# rev1.net
KiCad netlist of a schematic drawn in EAGLE
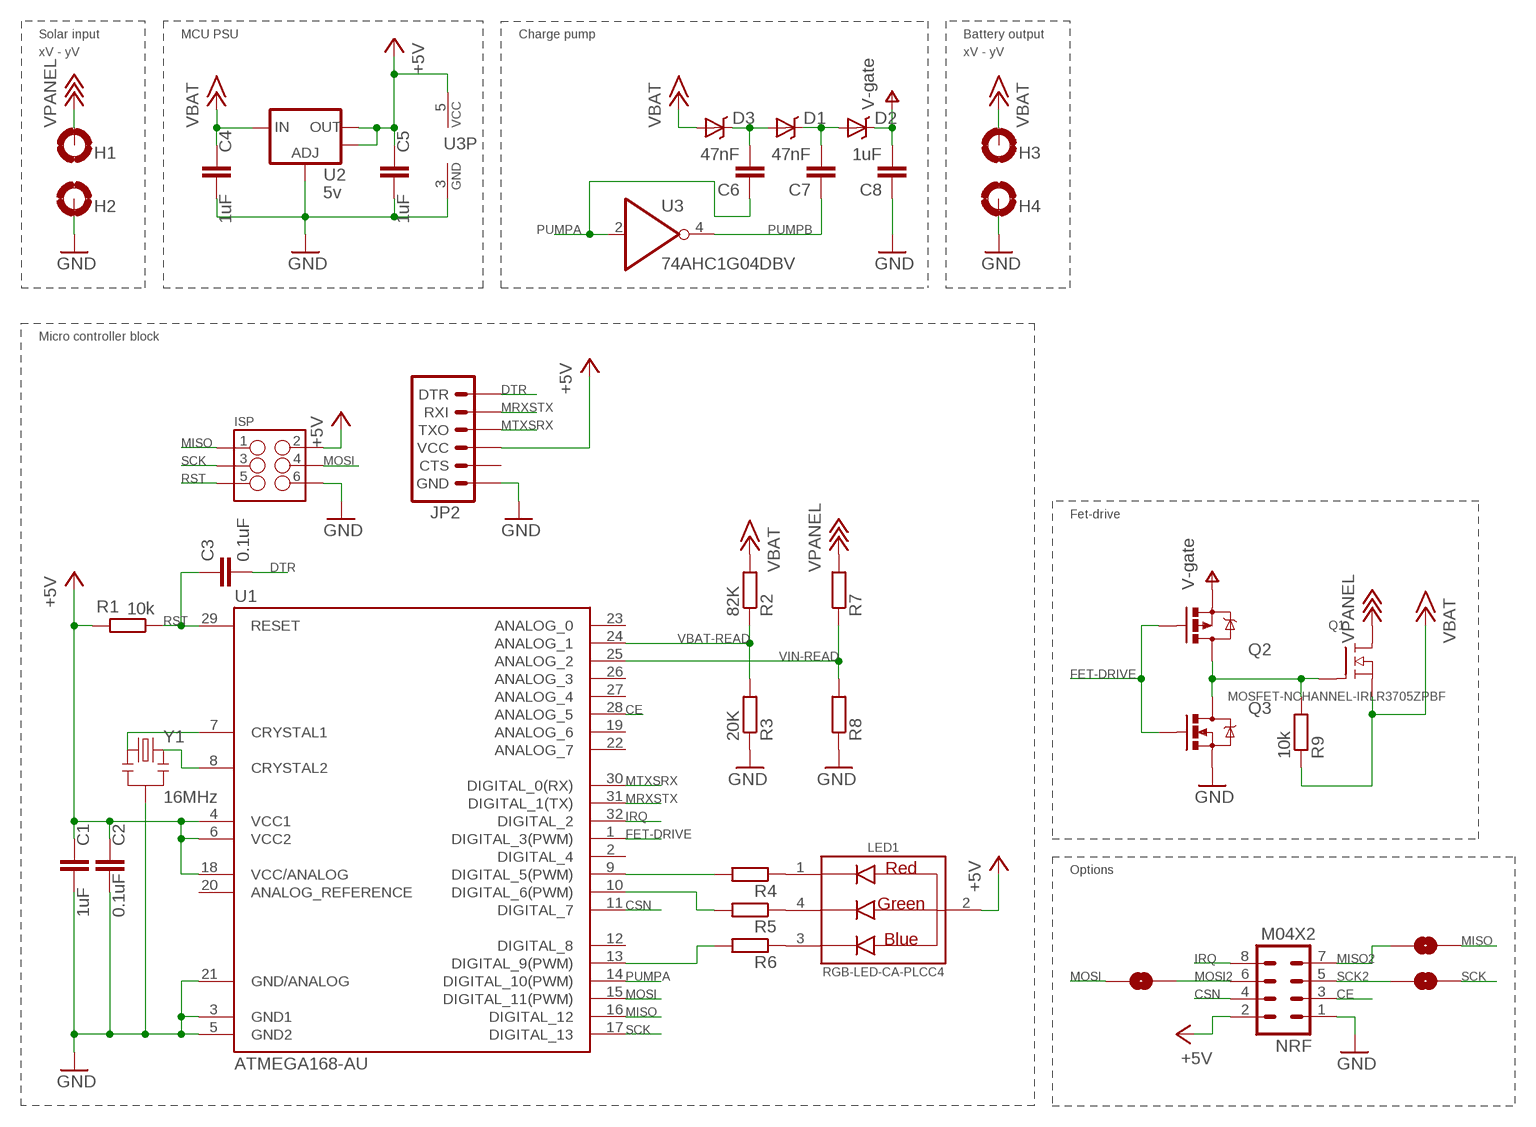
[diagram p0: schematic, sheet 1]

(export (version "E")
  (design (tool "Eeschema 10.0.6"))
  (components
    (comp (ref "C1")
      (value "1uF")
      (footprint "eagle-import:C0603K")
      (libsource (lib "eagle-import") (part "C-EUC0603K"))
    )
    (comp (ref "C2")
      (value "0.1uF")
      (footprint "eagle-import:C0603K")
      (libsource (lib "eagle-import") (part "C-EUC0603K"))
    )
    (comp (ref "C3")
      (value "0.1uF")
      (footprint "eagle-import:C0603K")
      (libsource (lib "eagle-import") (part "C-EUC0603K"))
    )
    (comp (ref "C4")
      (value "1uF")
      (footprint "eagle-import:C0603K")
      (libsource (lib "eagle-import") (part "C-EUC0603K"))
    )
    (comp (ref "C5")
      (value "1uF")
      (footprint "eagle-import:C0603K")
      (libsource (lib "eagle-import") (part "C-EUC0603K"))
    )
    (comp (ref "C6")
      (value "47nF")
      (footprint "eagle-import:C0603K")
      (libsource (lib "eagle-import") (part "C-EUC0603K"))
    )
    (comp (ref "C7")
      (value "47nF")
      (footprint "eagle-import:C0603K")
      (libsource (lib "eagle-import") (part "C-EUC0603K"))
    )
    (comp (ref "C8")
      (value "1uF")
      (footprint "eagle-import:C0603K")
      (libsource (lib "eagle-import") (part "C-EUC0603K"))
    )
    (comp (ref "D1")
      (value "DIODE-SCHOTTKY")
      (footprint "eagle-import:SOD-523")
      (libsource (lib "eagle-import") (part "DIODE-SCHOTTKY"))
    )
    (comp (ref "D2")
      (value "DIODE-SCHOTTKY")
      (footprint "eagle-import:SOD-523")
      (libsource (lib "eagle-import") (part "DIODE-SCHOTTKY"))
    )
    (comp (ref "D3")
      (value "DIODE-SCHOTTKY")
      (footprint "eagle-import:SOD-523")
      (libsource (lib "eagle-import") (part "DIODE-SCHOTTKY"))
    )
    (comp (ref "H1")
      (value "MOUNT-PAD-ROUND3.0")
      (footprint "eagle-import:3,0-PAD")
      (libsource (lib "eagle-import") (part "MOUNT-PAD-ROUND3.0"))
    )
    (comp (ref "H2")
      (value "MOUNT-PAD-ROUND3.0")
      (footprint "eagle-import:3,0-PAD")
      (libsource (lib "eagle-import") (part "MOUNT-PAD-ROUND3.0"))
    )
    (comp (ref "H3")
      (value "MOUNT-PAD-ROUND3.0")
      (footprint "eagle-import:3,0-PAD")
      (libsource (lib "eagle-import") (part "MOUNT-PAD-ROUND3.0"))
    )
    (comp (ref "H4")
      (value "MOUNT-PAD-ROUND3.0")
      (footprint "eagle-import:3,0-PAD")
      (libsource (lib "eagle-import") (part "MOUNT-PAD-ROUND3.0"))
    )
    (comp (ref "ISP")
      (value "M03X22X3_SILK_SM")
      (footprint "eagle-import:2X3")
      (libsource (lib "eagle-import") (part "M03X22X3_SILK_SM"))
    )
    (comp (ref "JP2")
      (value "ARDUINO_SERIAL_PROGRAMLOCK")
      (footprint "eagle-import:1X06_LOCK")
      (libsource (lib "eagle-import") (part "ARDUINO_SERIAL_PROGRAMLOCK"))
    )
    (comp (ref "LED1")
      (value "RGB-LED-CA-PLCC4")
      (footprint "eagle-import:PLCC4")
      (libsource (lib "eagle-import") (part "RGB-LED-CA-PLCC4"))
    )
    (comp (ref "NRF")
      (value "M04X2")
      (footprint "eagle-import:2X4")
      (libsource (lib "eagle-import") (part "M04X2"))
    )
    (comp (ref "Q1")
      (value "MOSFET-NCHANNEL-IRLR3705ZPBF")
      (footprint "eagle-import:DPAK")
      (libsource (lib "eagle-import") (part "MOSFET-NCHANNEL-IRLR3705ZPBF"))
    )
    (comp (ref "Q2")
      (value "MOSFET-PCHANNEL")
      (footprint "eagle-import:SOT23")
      (libsource (lib "eagle-import") (part "MOSFET-PCHANNEL"))
    )
    (comp (ref "Q3")
      (value "MOSFET-NCHANNELBSS138")
      (footprint "eagle-import:SOT23")
      (libsource (lib "eagle-import") (part "MOSFET-NCHANNELBSS138"))
    )
    (comp (ref "R1")
      (value "10k")
      (footprint "eagle-import:R0603")
      (libsource (lib "eagle-import") (part "R-EU_R0603"))
    )
    (comp (ref "R2")
      (value "82K")
      (footprint "eagle-import:R0603")
      (libsource (lib "eagle-import") (part "R-EU_R0603"))
    )
    (comp (ref "R3")
      (value "20K")
      (footprint "eagle-import:R0603")
      (libsource (lib "eagle-import") (part "R-EU_R0603"))
    )
    (comp (ref "R4")
      (value "R-EU_R0603")
      (footprint "eagle-import:R0603")
      (libsource (lib "eagle-import") (part "R-EU_R0603"))
    )
    (comp (ref "R5")
      (value "R-EU_R0603")
      (footprint "eagle-import:R0603")
      (libsource (lib "eagle-import") (part "R-EU_R0603"))
    )
    (comp (ref "R6")
      (value "R-EU_R0603")
      (footprint "eagle-import:R0603")
      (libsource (lib "eagle-import") (part "R-EU_R0603"))
    )
    (comp (ref "R7")
      (value "R-EU_R0603")
      (footprint "eagle-import:R0603")
      (libsource (lib "eagle-import") (part "R-EU_R0603"))
    )
    (comp (ref "R8")
      (value "R-EU_R0603")
      (footprint "eagle-import:R0603")
      (libsource (lib "eagle-import") (part "R-EU_R0603"))
    )
    (comp (ref "R9")
      (value "10k")
      (footprint "eagle-import:R0603")
      (libsource (lib "eagle-import") (part "R-EU_R0603"))
    )
    (comp (ref "SJ2")
      (value "SOLDERJUMPERNO")
      (footprint "eagle-import:SJ_2S-NO")
      (libsource (lib "eagle-import") (part "SOLDERJUMPERNO"))
    )
    (comp (ref "SJ5")
      (value "SOLDERJUMPERNO")
      (footprint "eagle-import:SJ_2S-NO")
      (libsource (lib "eagle-import") (part "SOLDERJUMPERNO"))
    )
    (comp (ref "SJ6")
      (value "SOLDERJUMPERNO")
      (footprint "eagle-import:SJ_2S-NO")
      (libsource (lib "eagle-import") (part "SOLDERJUMPERNO"))
    )
    (comp (ref "U1")
      (value "ATMEGA168-AU")
      (footprint "eagle-import:TQFP32-08")
      (libsource (lib "eagle-import") (part "ATMEGA168-AU"))
    )
    (comp (ref "U2")
      (value "5v")
      (footprint "eagle-import:SOT223")
      (libsource (lib "eagle-import") (part "V_REG_LM1117SOT223"))
    )
    (comp (ref "U3")
      (value "74AHC1G04DBV")
      (footprint "eagle-import:SOT23-5")
      (libsource (lib "eagle-import") (part "741G04DBVAHC"))
    )
    (comp (ref "Y1")
      (value "16MHz")
      (footprint "eagle-import:RESONATOR-SMD")
      (libsource (lib "eagle-import") (part "RESONATOR16MHZ"))
    )
  )
  (nets
    (net (code "1") (name "+5V") (class "Default")
      (node (ref "C1") (pin "1") (pinfunction "1_1") (pintype "passive"))
      (node (ref "C2") (pin "1") (pinfunction "1_1") (pintype "passive"))
      (node (ref "C5") (pin "1") (pinfunction "1_1") (pintype "passive"))
      (node (ref "ISP") (pin "2") (pinfunction "2_2") (pintype "bidirectional"))
      (node (ref "JP2") (pin "4") (pinfunction "VCC_4") (pintype "passive"))
      (node (ref "LED1") (pin "2") (pinfunction "CA_2") (pintype "bidirectional"))
      (node (ref "NRF") (pin "2") (pinfunction "2_2") (pintype "passive"))
      (node (ref "R1") (pin "2") (pinfunction "2_2") (pintype "passive"))
      (node (ref "U1") (pin "18") (pinfunction "VCC/ANALOG_18") (pintype "passive"))
      (node (ref "U1") (pin "4") (pinfunction "VCC1_4") (pintype "power_in"))
      (node (ref "U1") (pin "6") (pinfunction "VCC2_6") (pintype "power_in"))
      (node (ref "U2") (pin "2") (pinfunction "OUT_2") (pintype "output"))
      (node (ref "U2") (pin "4") (pinfunction "OUT_4") (pintype "output"))
      (node (ref "U3") (pin "5") (pinfunction "VCC_5") (pintype "power_in"))
    )
    (net (code "2") (name "/CE") (class "Default")
      (node (ref "NRF") (pin "3") (pinfunction "3_3") (pintype "passive"))
      (node (ref "U1") (pin "28") (pinfunction "ANALOG_5_28") (pintype "bidirectional"))
    )
    (net (code "3") (name "/CSN") (class "Default")
      (node (ref "NRF") (pin "4") (pinfunction "4_4") (pintype "passive"))
      (node (ref "U1") (pin "11") (pinfunction "DIGITAL_7_11") (pintype "bidirectional"))
    )
    (net (code "4") (name "/DTR") (class "Default")
      (node (ref "C3") (pin "2") (pinfunction "2_2") (pintype "passive"))
      (node (ref "JP2") (pin "1") (pinfunction "DTR_1") (pintype "passive"))
    )
    (net (code "5") (name "/FET-DRIVE") (class "Default")
      (node (ref "Q2") (pin "1") (pinfunction "G_1") (pintype "passive"))
      (node (ref "Q3") (pin "1") (pinfunction "G_1") (pintype "passive"))
      (node (ref "U1") (pin "1") (pinfunction "DIGITAL_3(PWM)_1") (pintype "bidirectional"))
    )
    (net (code "6") (name "/IRQ") (class "Default")
      (node (ref "NRF") (pin "8") (pinfunction "8_8") (pintype "passive"))
      (node (ref "U1") (pin "32") (pinfunction "DIGITAL_2_32") (pintype "bidirectional"))
    )
    (net (code "7") (name "/MISO") (class "Default")
      (node (ref "ISP") (pin "1") (pinfunction "1_1") (pintype "bidirectional"))
      (node (ref "SJ6") (pin "2") (pinfunction "2_2") (pintype "passive"))
      (node (ref "U1") (pin "16") (pinfunction "DIGITAL_12_16") (pintype "bidirectional"))
    )
    (net (code "8") (name "/MISO2") (class "Default")
      (node (ref "NRF") (pin "7") (pinfunction "7_7") (pintype "passive"))
      (node (ref "SJ6") (pin "1") (pinfunction "1_1") (pintype "passive"))
    )
    (net (code "9") (name "/MOSI") (class "Default")
      (node (ref "ISP") (pin "4") (pinfunction "4_4") (pintype "bidirectional"))
      (node (ref "SJ2") (pin "1") (pinfunction "1_1") (pintype "passive"))
      (node (ref "U1") (pin "15") (pinfunction "DIGITAL_11(PWM)_15") (pintype "bidirectional"))
    )
    (net (code "10") (name "/MOSI2") (class "Default")
      (node (ref "NRF") (pin "6") (pinfunction "6_6") (pintype "passive"))
      (node (ref "SJ2") (pin "2") (pinfunction "2_2") (pintype "passive"))
    )
    (net (code "11") (name "/MRXSTX") (class "Default")
      (node (ref "JP2") (pin "2") (pinfunction "RXI_2") (pintype "passive"))
      (node (ref "U1") (pin "31") (pinfunction "DIGITAL_1(TX)_31") (pintype "bidirectional"))
    )
    (net (code "12") (name "/MTXSRX") (class "Default")
      (node (ref "JP2") (pin "3") (pinfunction "TXO_3") (pintype "passive"))
      (node (ref "U1") (pin "30") (pinfunction "DIGITAL_0(RX)_30") (pintype "bidirectional"))
    )
    (net (code "13") (name "/PUMPA") (class "Default")
      (node (ref "C6") (pin "1") (pinfunction "1_1") (pintype "passive"))
      (node (ref "U1") (pin "14") (pinfunction "DIGITAL_10(PWM)_14") (pintype "bidirectional"))
      (node (ref "U3") (pin "2") (pinfunction "I_2") (pintype "input"))
    )
    (net (code "14") (name "/PUMPB") (class "Default")
      (node (ref "C7") (pin "1") (pinfunction "1_1") (pintype "passive"))
      (node (ref "U3") (pin "4") (pinfunction "O_4") (pintype "output"))
    )
    (net (code "15") (name "/RST") (class "Default")
      (node (ref "C3") (pin "1") (pinfunction "1_1") (pintype "passive"))
      (node (ref "ISP") (pin "5") (pinfunction "5_5") (pintype "bidirectional"))
      (node (ref "R1") (pin "1") (pinfunction "1_1") (pintype "passive"))
      (node (ref "U1") (pin "29") (pinfunction "RESET_29") (pintype "bidirectional"))
    )
    (net (code "16") (name "/SCK") (class "Default")
      (node (ref "ISP") (pin "3") (pinfunction "3_3") (pintype "bidirectional"))
      (node (ref "SJ5") (pin "2") (pinfunction "2_2") (pintype "passive"))
      (node (ref "U1") (pin "17") (pinfunction "DIGITAL_13_17") (pintype "bidirectional"))
    )
    (net (code "17") (name "/SCK2") (class "Default")
      (node (ref "NRF") (pin "5") (pinfunction "5_5") (pintype "passive"))
      (node (ref "SJ5") (pin "1") (pinfunction "1_1") (pintype "passive"))
    )
    (net (code "18") (name "/VBAT-READ") (class "Default")
      (node (ref "R2") (pin "1") (pinfunction "1_1") (pintype "passive"))
      (node (ref "R3") (pin "2") (pinfunction "2_2") (pintype "passive"))
      (node (ref "U1") (pin "24") (pinfunction "ANALOG_1_24") (pintype "bidirectional"))
    )
    (net (code "19") (name "/VIN-READ") (class "Default")
      (node (ref "R7") (pin "1") (pinfunction "1_1") (pintype "passive"))
      (node (ref "R8") (pin "2") (pinfunction "2_2") (pintype "passive"))
      (node (ref "U1") (pin "25") (pinfunction "ANALOG_2_25") (pintype "bidirectional"))
    )
    (net (code "20") (name "GND") (class "Default")
      (node (ref "C1") (pin "2") (pinfunction "2_2") (pintype "passive"))
      (node (ref "C2") (pin "2") (pinfunction "2_2") (pintype "passive"))
      (node (ref "C4") (pin "2") (pinfunction "2_2") (pintype "passive"))
      (node (ref "C5") (pin "2") (pinfunction "2_2") (pintype "passive"))
      (node (ref "C8") (pin "1") (pinfunction "1_1") (pintype "passive"))
      (node (ref "H2") (pin "B3,0") (pinfunction "MOUNT_B3,0") (pintype "passive"))
      (node (ref "H4") (pin "B3,0") (pinfunction "MOUNT_B3,0") (pintype "passive"))
      (node (ref "ISP") (pin "6") (pinfunction "6_6") (pintype "bidirectional"))
      (node (ref "JP2") (pin "6") (pinfunction "GND_6") (pintype "passive"))
      (node (ref "NRF") (pin "1") (pinfunction "1_1") (pintype "passive"))
      (node (ref "Q3") (pin "2") (pinfunction "S_2") (pintype "passive"))
      (node (ref "R3") (pin "1") (pinfunction "1_1") (pintype "passive"))
      (node (ref "R8") (pin "1") (pinfunction "1_1") (pintype "passive"))
      (node (ref "U1") (pin "21") (pinfunction "GND/ANALOG_21") (pintype "power_in"))
      (node (ref "U1") (pin "3") (pinfunction "GND1_3") (pintype "power_in"))
      (node (ref "U1") (pin "5") (pinfunction "GND2_5") (pintype "power_in"))
      (node (ref "U2") (pin "1") (pinfunction "ADJ_1") (pintype "input"))
      (node (ref "U3") (pin "3") (pinfunction "GND_3") (pintype "power_in"))
      (node (ref "Y1") (pin "2") (pinfunction "2_2") (pintype "passive"))
    )
    (net (code "21") (name "Net-(C6-Pad2)") (class "Default")
      (node (ref "C6") (pin "2") (pinfunction "2_2") (pintype "passive"))
      (node (ref "D1") (pin "A") (pinfunction "A_A") (pintype "passive"))
      (node (ref "D3") (pin "C") (pinfunction "C_C") (pintype "passive"))
    )
    (net (code "22") (name "Net-(C7-Pad2)") (class "Default")
      (node (ref "C7") (pin "2") (pinfunction "2_2") (pintype "passive"))
      (node (ref "D1") (pin "C") (pinfunction "C_C") (pintype "passive"))
      (node (ref "D2") (pin "A") (pinfunction "A_A") (pintype "passive"))
    )
    (net (code "23") (name "Net-(LED1-BC)") (class "Default")
      (node (ref "LED1") (pin "3") (pinfunction "BC_3") (pintype "bidirectional"))
      (node (ref "R6") (pin "1") (pinfunction "1_1") (pintype "passive"))
    )
    (net (code "24") (name "Net-(LED1-GC)") (class "Default")
      (node (ref "LED1") (pin "4") (pinfunction "GC_4") (pintype "bidirectional"))
      (node (ref "R5") (pin "1") (pinfunction "1_1") (pintype "passive"))
    )
    (net (code "25") (name "Net-(LED1-RC)") (class "Default")
      (node (ref "LED1") (pin "1") (pinfunction "RC_1") (pintype "bidirectional"))
      (node (ref "R4") (pin "1") (pinfunction "1_1") (pintype "passive"))
    )
    (net (code "26") (name "Net-(Q1-G)") (class "Default")
      (node (ref "Q1") (pin "1") (pinfunction "G_1") (pintype "bidirectional"))
      (node (ref "Q2") (pin "3") (pinfunction "D_3") (pintype "passive"))
      (node (ref "Q3") (pin "3") (pinfunction "D_3") (pintype "passive"))
      (node (ref "R9") (pin "2") (pinfunction "2_2") (pintype "passive"))
    )
    (net (code "27") (name "Net-(U1-CRYSTAL1)") (class "Default")
      (node (ref "U1") (pin "7") (pinfunction "CRYSTAL1_7") (pintype "bidirectional"))
      (node (ref "Y1") (pin "1") (pinfunction "1_1") (pintype "passive"))
    )
    (net (code "28") (name "Net-(U1-CRYSTAL2)") (class "Default")
      (node (ref "U1") (pin "8") (pinfunction "CRYSTAL2_8") (pintype "bidirectional"))
      (node (ref "Y1") (pin "3") (pinfunction "3_3") (pintype "passive"))
    )
    (net (code "29") (name "Net-(U1-DIGITAL_5(PWM))") (class "Default")
      (node (ref "R4") (pin "2") (pinfunction "2_2") (pintype "passive"))
      (node (ref "U1") (pin "9") (pinfunction "DIGITAL_5(PWM)_9") (pintype "bidirectional"))
    )
    (net (code "30") (name "Net-(U1-DIGITAL_6(PWM))") (class "Default")
      (node (ref "R5") (pin "2") (pinfunction "2_2") (pintype "passive"))
      (node (ref "U1") (pin "10") (pinfunction "DIGITAL_6(PWM)_10") (pintype "bidirectional"))
    )
    (net (code "31") (name "Net-(U1-DIGITAL_9(PWM))") (class "Default")
      (node (ref "R6") (pin "2") (pinfunction "2_2") (pintype "passive"))
      (node (ref "U1") (pin "13") (pinfunction "DIGITAL_9(PWM)_13") (pintype "bidirectional"))
    )
    (net (code "32") (name "V-gate") (class "Default")
      (node (ref "C8") (pin "2") (pinfunction "2_2") (pintype "passive"))
      (node (ref "D2") (pin "C") (pinfunction "C_C") (pintype "passive"))
      (node (ref "Q2") (pin "2") (pinfunction "S_2") (pintype "passive"))
    )
    (net (code "33") (name "VBAT") (class "Default")
      (node (ref "C4") (pin "1") (pinfunction "1_1") (pintype "passive"))
      (node (ref "D3") (pin "A") (pinfunction "A_A") (pintype "passive"))
      (node (ref "H3") (pin "B3,0") (pinfunction "MOUNT_B3,0") (pintype "passive"))
      (node (ref "Q1") (pin "2") (pinfunction "S_2") (pintype "bidirectional"))
      (node (ref "R2") (pin "2") (pinfunction "2_2") (pintype "passive"))
      (node (ref "R9") (pin "1") (pinfunction "1_1") (pintype "passive"))
      (node (ref "U2") (pin "3") (pinfunction "IN_3") (pintype "input"))
    )
    (net (code "34") (name "VPANEL") (class "Default")
      (node (ref "H1") (pin "B3,0") (pinfunction "MOUNT_B3,0") (pintype "passive"))
      (node (ref "Q1") (pin "TAB") (pinfunction "D_TAB") (pintype "bidirectional"))
      (node (ref "R7") (pin "2") (pinfunction "2_2") (pintype "passive"))
    )
    (net (code "35") (name "unconnected-(JP2-CTS-Pad5)") (class "Default")
      (node (ref "JP2") (pin "5") (pinfunction "CTS_5") (pintype "passive"))
    )
    (net (code "36") (name "unconnected-(U1-ANALOG_0-Pad23)") (class "Default")
      (node (ref "U1") (pin "23") (pinfunction "ANALOG_0_23") (pintype "bidirectional"))
    )
    (net (code "37") (name "unconnected-(U1-ANALOG_3-Pad26)") (class "Default")
      (node (ref "U1") (pin "26") (pinfunction "ANALOG_3_26") (pintype "bidirectional"))
    )
    (net (code "38") (name "unconnected-(U1-ANALOG_4-Pad27)") (class "Default")
      (node (ref "U1") (pin "27") (pinfunction "ANALOG_4_27") (pintype "bidirectional"))
    )
    (net (code "39") (name "unconnected-(U1-ANALOG_6-Pad19)") (class "Default")
      (node (ref "U1") (pin "19") (pinfunction "ANALOG_6_19") (pintype "passive"))
    )
    (net (code "40") (name "unconnected-(U1-ANALOG_7-Pad22)") (class "Default")
      (node (ref "U1") (pin "22") (pinfunction "ANALOG_7_22") (pintype "passive"))
    )
    (net (code "41") (name "unconnected-(U1-ANALOG_REFERENCE-Pad20)") (class "Default")
      (node (ref "U1") (pin "20") (pinfunction "ANALOG_REFERENCE_20") (pintype "passive"))
    )
    (net (code "42") (name "unconnected-(U1-DIGITAL_4-Pad2)") (class "Default")
      (node (ref "U1") (pin "2") (pinfunction "DIGITAL_4_2") (pintype "bidirectional"))
    )
    (net (code "43") (name "unconnected-(U1-DIGITAL_8-Pad12)") (class "Default")
      (node (ref "U1") (pin "12") (pinfunction "DIGITAL_8_12") (pintype "bidirectional"))
    )
  )
)
